# 12_HEADERS.net
KiCad netlist of a schematic drawn in Altium Designer
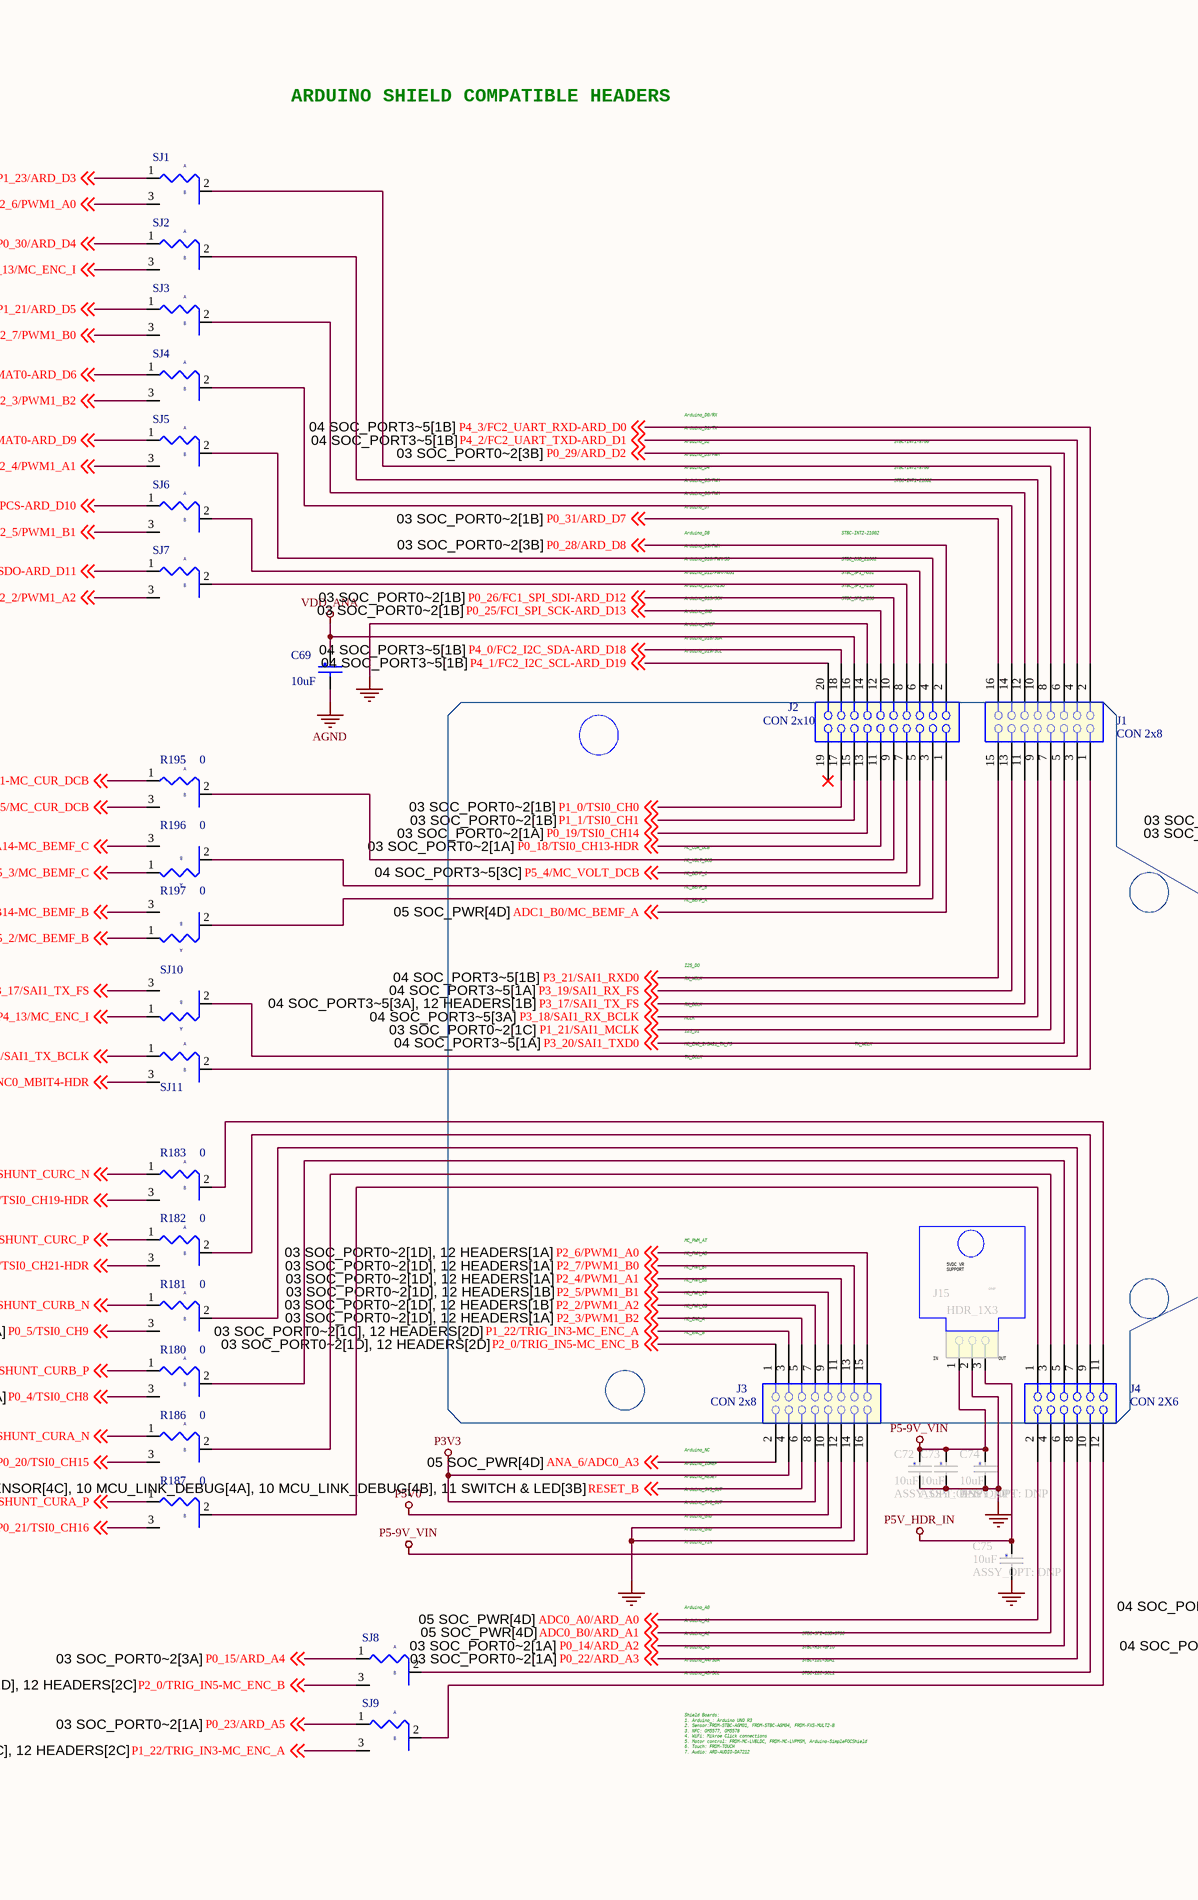
[diagram p0: 12 HEADERS.SchDoc, left]
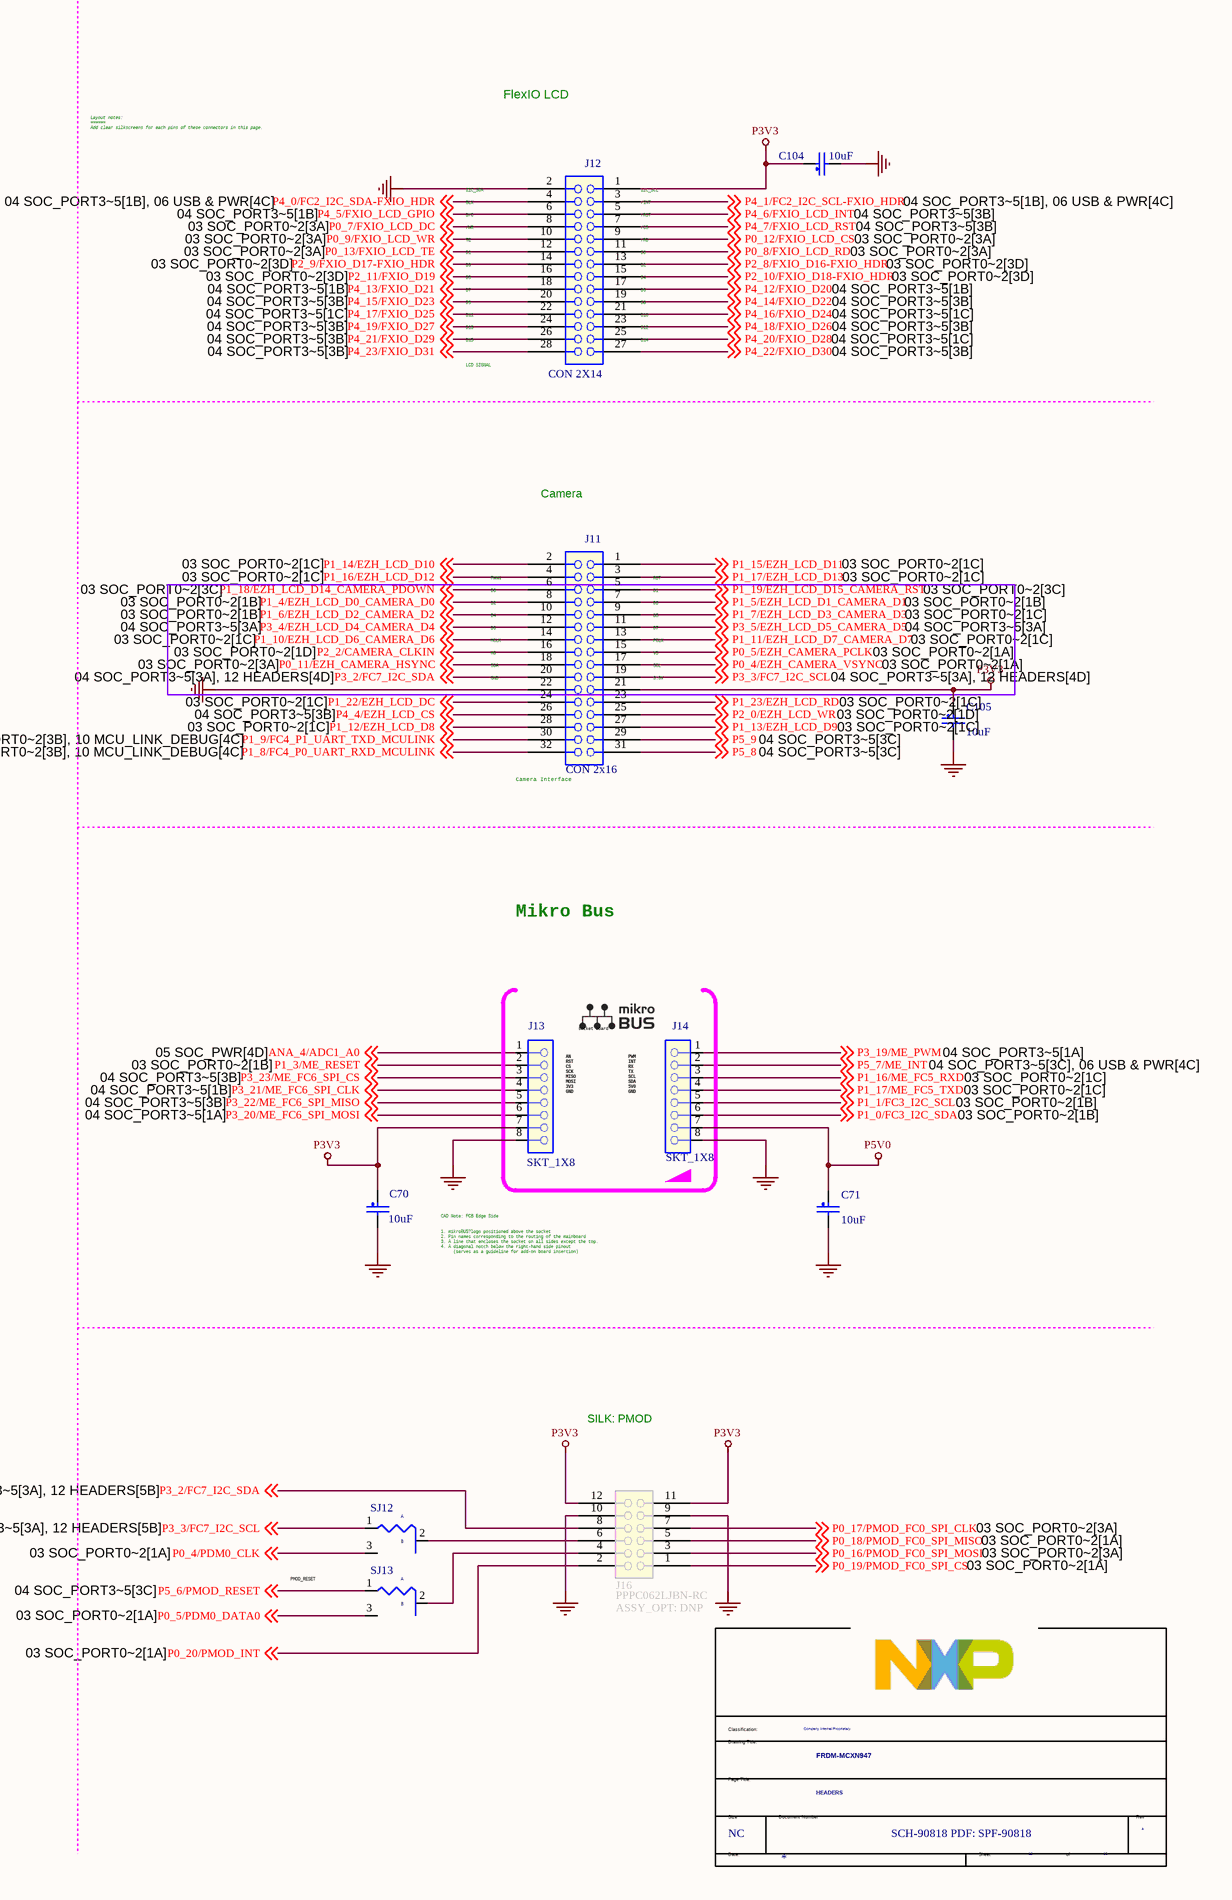
[diagram p1: 12 HEADERS.SchDoc, right]

(export (version "E")
  (design (tool "Eeschema 10.0.6"))
  (components
    (comp (ref "*")
      (value "TitleBlock_FS")
      (fields
        (field (name "DOC") "SCH-90818 PDF: SPF-90818")
        (field (name "REVCODE") "A")
        (field (name "TITLE") "FRDM-MCXN947")
        (field (name "PAGE SIZE") "NC")
        (field (name "PAGE NUMBER") "12")
        (field (name "PAGE COUNT") "13")
        (field (name "PAGETITLE") "HEADERS")
        (field (name "CLASSIFICATION") "Company Internal/Proprietary")
      )
      (libsource (lib "*") (part "TitleBlock_FS"))
    )
    (comp (ref "C69")
      (value "10uF")
      (footprint "CC0603_OV")
      (description "CAP CER 10uF 25V 10% X5R 0603")
      (fields (field (name "TOLERANCE") "10%"))
      (libsource (lib "*") (part "CAP_NP"))
    )
    (comp (ref "C70")
      (value "10uF")
      (footprint "CC0603_OV")
      (description "CAP CER 10uF 25V 10% X5R 0603")
      (fields (field (name "TOLERANCE") "10%"))
      (libsource (lib "*") (part "CAP_NP"))
    )
    (comp (ref "C71")
      (value "10uF")
      (footprint "CC0603_OV")
      (description "CAP CER 10uF 25V 10% X5R 0603")
      (fields (field (name "TOLERANCE") "10%"))
      (libsource (lib "*") (part "CAP_NP"))
    )
    (comp (ref "C72")
      (value "10uF")
      (footprint "CC0603_OV")
      (description "CAP CER 10uF 25V 10% X5R 0603")
      (fields (field (name "ASSY_OPT") "DNP") (field (name "TOLERANCE") "10%"))
      (libsource (lib "*") (part "CAP_NP"))
    )
    (comp (ref "C73")
      (value "10uF")
      (footprint "CC0603_OV")
      (description "CAP CER 10uF 25V 10% X5R 0603")
      (fields (field (name "ASSY_OPT") "DNP") (field (name "TOLERANCE") "10%"))
      (libsource (lib "*") (part "CAP_NP"))
    )
    (comp (ref "C74")
      (value "10uF")
      (footprint "CC0603_OV")
      (description "CAP CER 10uF 25V 10% X5R 0603")
      (fields (field (name "ASSY_OPT") "DNP") (field (name "TOLERANCE") "10%"))
      (libsource (lib "*") (part "CAP_NP"))
    )
    (comp (ref "C75")
      (value "10uF")
      (footprint "CC0603_OV")
      (description "CAP CER 10uF 25V 10% X5R 0603")
      (fields (field (name "ASSY_OPT") "DNP") (field (name "TOLERANCE") "10%"))
      (libsource (lib "*") (part "CAP_NP"))
    )
    (comp (ref "C104")
      (value "10uF")
      (footprint "CC0603_OV")
      (description "CAP CER 10uF 25V 10% X5R 0603")
      (fields (field (name "TOLERANCE") "10%"))
      (libsource (lib "*") (part "CAP_NP"))
    )
    (comp (ref "C105")
      (value "10uF")
      (footprint "CC0603_OV")
      (description "CAP CER 10uF 25V 10% X5R 0603")
      (fields (field (name "TOLERANCE") "10%"))
      (libsource (lib "*") (part "CAP_NP"))
    )
    (comp (ref "J1")
      (value "CON 2x8")
      (footprint "con_2x8_skt_100_th")
      (description "CON 2X8 SKT SHRD TH 100MIL CTR 345H AU 126L")
      (libsource (lib "*") (part "CONN_HDR_8X2"))
    )
    (comp (ref "J2")
      (value "CON 2x10")
      (footprint "con_skt2x10_th")
      (description "CON 2X10 SKT SHRD TH 100MIL CTR 345H AU 126L")
      (libsource (lib "*") (part "CONN_HDR_10X2"))
    )
    (comp (ref "J3")
      (value "CON 2x8")
      (footprint "con_2x8_skt_100_th")
      (description "CON 2X8 SKT SHRD TH 100MIL CTR 345H AU 126L")
      (libsource (lib "") (part "CONN_HDR_8X2_1"))
    )
    (comp (ref "J4")
      (value "CON 2X6")
      (footprint "con_skt2x6_th_126l")
      (description "CON 2X6 SKT SHRD TH 100MIL CTR 345H AU 126L")
      (libsource (lib "*") (part "CONN_HDR_6X2"))
    )
    (comp (ref "J11")
      (value "CON 2x16")
      (footprint "con_skt_32f_100_th")
      (description "CON 2X16 SKT SHRD TH 100MIL CTR 345H AU 126L")
      (fields (field (name "SILK") "Camera"))
      (libsource (lib "*") (part "CONN_HDR_16X2"))
    )
    (comp (ref "J12")
      (value "CON 2X14")
      (footprint "con_skt2x14_th_126l")
      (description "CON 2X14 SKT SHRD TH 100MIL CTR 345H AU 126L")
      (fields (field (name "SILK") "FlexIO LCD"))
      (libsource (lib "*") (part "CONN_HDR_14X2"))
    )
    (comp (ref "J13")
      (value "SKT_1X8")
      (footprint "con_1x8_skt_2p54_th_126l")
      (description "CON 1X8 SKT TH 100MIL SP 344H AU 118L")
      (libsource (lib "*") (part "CONN_HDR_8X1"))
    )
    (comp (ref "J14")
      (value "SKT_1X8")
      (footprint "con_1x8_skt_2p54_th_126l")
      (description "CON 1X8 SKT TH 100MIL SP 344H AU 118L")
      (libsource (lib "") (part "CONN_HDR_8X1_1"))
    )
    (comp (ref "J15")
      (value "HDR_1X3")
      (footprint "HDR103")
      (description "HDR 1X3 TH 100MIL SP 330H AU 98L")
      (fields (field (name "ASSY_OPT") "DNP"))
      (libsource (lib "*") (part "CONN_HDR_3X1"))
    )
    (comp (ref "J16")
      (value "PPPC062LJBN-RC")
      (footprint "skt2x6_100_th_ra")
      (description "CON 2X6 SKT RA TH 100MIL CTR 206H AU 124L")
      (fields (field (name "ASSY_OPT") "DNP") (field (name "SILK") "PMOD"))
      (libsource (lib "*") (part "CONN_HDR_6X2"))
    )
    (comp (ref "R180")
      (value "0")
      (footprint "R603-X2")
      (description "RES MF ZERO OHM 1/10W -- 0603")
      (libsource (lib "*") (part "RES_3PIN"))
    )
    (comp (ref "R181")
      (value "0")
      (footprint "R603-X2")
      (description "RES MF ZERO OHM 1/10W -- 0603")
      (libsource (lib "*") (part "RES_3PIN"))
    )
    (comp (ref "R182")
      (value "0")
      (footprint "R603-X2")
      (description "RES MF ZERO OHM 1/10W -- 0603")
      (libsource (lib "*") (part "RES_3PIN"))
    )
    (comp (ref "R183")
      (value "0")
      (footprint "R603-X2")
      (description "RES MF ZERO OHM 1/10W -- 0603")
      (libsource (lib "*") (part "RES_3PIN"))
    )
    (comp (ref "R186")
      (value "0")
      (footprint "R603-X2")
      (description "RES MF ZERO OHM 1/10W -- 0603")
      (libsource (lib "*") (part "RES_3PIN"))
    )
    (comp (ref "R187")
      (value "0")
      (footprint "R603-X2")
      (description "RES MF ZERO OHM 1/10W -- 0603")
      (libsource (lib "*") (part "RES_3PIN"))
    )
    (comp (ref "R195")
      (value "0")
      (footprint "R603-X2")
      (description "RES MF ZERO OHM 1/10W -- 0603")
      (libsource (lib "*") (part "RES_3PIN"))
    )
    (comp (ref "R196")
      (value "0")
      (footprint "R603-X2")
      (description "RES MF ZERO OHM 1/10W -- 0603")
      (libsource (lib "*") (part "RES_3PIN"))
    )
    (comp (ref "R197")
      (value "0")
      (footprint "R603-X2")
      (description "RES MF ZERO OHM 1/10W -- 0603")
      (libsource (lib "*") (part "RES_3PIN"))
    )
    (comp (ref "SJ1")
      (value "3 PIN 0402 JUMPER")
      (footprint "3pin_0402_solder_blob_jumper_short_psp_a")
      (description "SOLDER BLOB JUMPER 3PIN 1-2 SHORT 0402 - NO PART TO ORDER")
      (libsource (lib "*") (part "RES_3PIN"))
    )
    (comp (ref "SJ2")
      (value "3 PIN 0402 JUMPER")
      (footprint "3pin_0402_solder_blob_jumper_short_psp_a")
      (description "SOLDER BLOB JUMPER 3PIN 1-2 SHORT 0402 - NO PART TO ORDER")
      (libsource (lib "*") (part "RES_3PIN"))
    )
    (comp (ref "SJ3")
      (value "3 PIN 0402 JUMPER")
      (footprint "3pin_0402_solder_blob_jumper_short_psp_a")
      (description "SOLDER BLOB JUMPER 3PIN 1-2 SHORT 0402 - NO PART TO ORDER")
      (libsource (lib "*") (part "RES_3PIN"))
    )
    (comp (ref "SJ4")
      (value "3 PIN 0402 JUMPER")
      (footprint "3pin_0402_solder_blob_jumper_short_psp_a")
      (description "SOLDER BLOB JUMPER 3PIN 1-2 SHORT 0402 - NO PART TO ORDER")
      (libsource (lib "*") (part "RES_3PIN"))
    )
    (comp (ref "SJ5")
      (value "3 PIN 0402 JUMPER")
      (footprint "3pin_0402_solder_blob_jumper_short_psp_a")
      (description "SOLDER BLOB JUMPER 3PIN 1-2 SHORT 0402 - NO PART TO ORDER")
      (libsource (lib "*") (part "RES_3PIN"))
    )
    (comp (ref "SJ6")
      (value "3 PIN 0402 JUMPER")
      (footprint "3pin_0402_solder_blob_jumper_short_psp_a")
      (description "SOLDER BLOB JUMPER 3PIN 1-2 SHORT 0402 - NO PART TO ORDER")
      (libsource (lib "*") (part "RES_3PIN"))
    )
    (comp (ref "SJ7")
      (value "3 PIN 0402 JUMPER")
      (footprint "3pin_0402_solder_blob_jumper_short_psp_a")
      (description "SOLDER BLOB JUMPER 3PIN 1-2 SHORT 0402 - NO PART TO ORDER")
      (libsource (lib "*") (part "RES_3PIN"))
    )
    (comp (ref "SJ8")
      (value "3 PIN 0402 JUMPER")
      (footprint "3pin_0402_solder_blob_jumper_short_psp_a")
      (description "SOLDER BLOB JUMPER 3PIN 1-2 SHORT 0402 - NO PART TO ORDER")
      (libsource (lib "*") (part "RES_3PIN"))
    )
    (comp (ref "SJ9")
      (value "3 PIN 0402 JUMPER")
      (footprint "3pin_0402_solder_blob_jumper_short_psp_a")
      (description "SOLDER BLOB JUMPER 3PIN 1-2 SHORT 0402 - NO PART TO ORDER")
      (libsource (lib "*") (part "RES_3PIN"))
    )
    (comp (ref "SJ10")
      (value "3 PIN 0402 JUMPER")
      (footprint "3pin_0402_solder_blob_jumper_short_psp_a")
      (description "SOLDER BLOB JUMPER 3PIN 1-2 SHORT 0402 - NO PART TO ORDER")
      (libsource (lib "*") (part "RES_3PIN"))
    )
    (comp (ref "SJ11")
      (value "3 PIN 0402 JUMPER")
      (footprint "3pin_0402_solder_blob_jumper_short_psp_a")
      (description "SOLDER BLOB JUMPER 3PIN 1-2 SHORT 0402 - NO PART TO ORDER")
      (libsource (lib "*") (part "RES_3PIN"))
    )
    (comp (ref "SJ12")
      (value "3 PIN 0402 JUMPER")
      (footprint "3pin_0402_solder_blob_jumper_short_psp_a")
      (description "SOLDER BLOB JUMPER 3PIN 1-2 SHORT 0402 - NO PART TO ORDER")
      (libsource (lib "*") (part "RES_3PIN"))
    )
    (comp (ref "SJ13")
      (value "3 PIN 0402 JUMPER")
      (footprint "3pin_0402_solder_blob_jumper_short_psp_a")
      (description "SOLDER BLOB JUMPER 3PIN 1-2 SHORT 0402 - NO PART TO ORDER")
      (libsource (lib "*") (part "RES_3PIN"))
    )
  )
  (nets
    (net (code "1") (name "ADC0_A0{slash}ARD_A0") (class "Default")
      (node (ref "J4") (pin "2") (pinfunction "B1_2") (pintype "passive"))
    )
    (net (code "2") (name "ADC0_B0{slash}ARD_A1") (class "Default")
      (node (ref "J4") (pin "4") (pinfunction "B2_4") (pintype "passive"))
    )
    (net (code "3") (name "ADC1_B0{slash}MC_BEMF_A") (class "Default")
      (node (ref "J2") (pin "1") (pinfunction "1_1") (pintype "passive"))
    )
    (net (code "4") (name "AGND") (class "Default")
      (node (ref "C69") (pin "2") (pinfunction "2_2") (pintype "passive"))
    )
    (net (code "5") (name "ANA_4{slash}ADC1_A0") (class "Default")
      (node (ref "J13") (pin "1") (pinfunction "1_1") (pintype "passive"))
    )
    (net (code "6") (name "ANA_6{slash}ADC0_A3") (class "Default")
      (node (ref "J3") (pin "2") (pinfunction "B1_2") (pintype "passive"))
    )
    (net (code "7") (name "GND") (class "Default")
      (node (ref "C104") (pin "2") (pinfunction "2_2") (pintype "passive"))
      (node (ref "C105") (pin "2") (pinfunction "2_2") (pintype "passive"))
      (node (ref "C70") (pin "2") (pinfunction "2_2") (pintype "passive"))
      (node (ref "C71") (pin "2") (pinfunction "2_2") (pintype "passive"))
      (node (ref "C72") (pin "2") (pinfunction "2_2") (pintype "passive"))
      (node (ref "C73") (pin "2") (pinfunction "2_2") (pintype "passive"))
      (node (ref "C74") (pin "2") (pinfunction "2_2") (pintype "passive"))
      (node (ref "C75") (pin "2") (pinfunction "2_2") (pintype "passive"))
      (node (ref "J11") (pin "22") (pinfunction "B11_22") (pintype "passive"))
      (node (ref "J12") (pin "2") (pinfunction "B1_2") (pintype "passive"))
      (node (ref "J13") (pin "8") (pinfunction "8_8") (pintype "passive"))
      (node (ref "J14") (pin "8") (pinfunction "8_8") (pintype "passive"))
      (node (ref "J15") (pin "2") (pinfunction "2_2") (pintype "passive"))
      (node (ref "J16") (pin "10") (pinfunction "B5_10") (pintype "passive"))
      (node (ref "J16") (pin "9") (pinfunction "A5_9") (pintype "passive"))
      (node (ref "J2") (pin "14") (pinfunction "14_14") (pintype "passive"))
      (node (ref "J3") (pin "12") (pinfunction "B6_12") (pintype "passive"))
      (node (ref "J3") (pin "14") (pinfunction "B7_14") (pintype "passive"))
    )
    (net (code "8") (name "Net-(J1-A1)") (class "Default")
      (node (ref "J1") (pin "1") (pinfunction "A1_1") (pintype "passive"))
      (node (ref "SJ11") (pin "2") (pinfunction "2_2") (pintype "passive"))
    )
    (net (code "9") (name "Net-(J1-A2)") (class "Default")
      (node (ref "J1") (pin "3") (pinfunction "A2_3") (pintype "passive"))
      (node (ref "SJ10") (pin "2") (pinfunction "2_2") (pintype "passive"))
    )
    (net (code "10") (name "Net-(J1-B4)") (class "Default")
      (node (ref "J1") (pin "8") (pinfunction "B4_8") (pintype "passive"))
      (node (ref "SJ1") (pin "2") (pinfunction "2_2") (pintype "passive"))
    )
    (net (code "11") (name "Net-(J1-B5)") (class "Default")
      (node (ref "J1") (pin "10") (pinfunction "B5_10") (pintype "passive"))
      (node (ref "SJ2") (pin "2") (pinfunction "2_2") (pintype "passive"))
    )
    (net (code "12") (name "Net-(J1-B6)") (class "Default")
      (node (ref "J1") (pin "12") (pinfunction "B6_12") (pintype "passive"))
      (node (ref "SJ3") (pin "2") (pinfunction "2_2") (pintype "passive"))
    )
    (net (code "13") (name "Net-(J1-B7)") (class "Default")
      (node (ref "J1") (pin "14") (pinfunction "B7_14") (pintype "passive"))
      (node (ref "SJ4") (pin "2") (pinfunction "2_2") (pintype "passive"))
    )
    (net (code "14") (name "Net-(J2-Pad3)") (class "Default")
      (node (ref "J2") (pin "3") (pinfunction "3_3") (pintype "passive"))
      (node (ref "R197") (pin "2") (pinfunction "2_2") (pintype "passive"))
    )
    (net (code "15") (name "Net-(J2-Pad4)") (class "Default")
      (node (ref "J2") (pin "4") (pinfunction "4_4") (pintype "passive"))
      (node (ref "SJ5") (pin "2") (pinfunction "2_2") (pintype "passive"))
    )
    (net (code "16") (name "Net-(J2-Pad5)") (class "Default")
      (node (ref "J2") (pin "5") (pinfunction "5_5") (pintype "passive"))
      (node (ref "R196") (pin "2") (pinfunction "2_2") (pintype "passive"))
    )
    (net (code "17") (name "Net-(J2-Pad6)") (class "Default")
      (node (ref "J2") (pin "6") (pinfunction "6_6") (pintype "passive"))
      (node (ref "SJ6") (pin "2") (pinfunction "2_2") (pintype "passive"))
    )
    (net (code "18") (name "Net-(J2-Pad8)") (class "Default")
      (node (ref "J2") (pin "8") (pinfunction "8_8") (pintype "passive"))
      (node (ref "SJ7") (pin "2") (pinfunction "2_2") (pintype "passive"))
    )
    (net (code "19") (name "Net-(J2-Pad9)") (class "Default")
      (node (ref "J2") (pin "9") (pinfunction "9_9") (pintype "passive"))
      (node (ref "R195") (pin "2") (pinfunction "2_2") (pintype "passive"))
    )
    (net (code "20") (name "Net-(J4-A1)") (class "Default")
      (node (ref "J4") (pin "1") (pinfunction "A1_1") (pintype "passive"))
      (node (ref "R187") (pin "2") (pinfunction "2_2") (pintype "passive"))
    )
    (net (code "21") (name "Net-(J4-A2)") (class "Default")
      (node (ref "J4") (pin "3") (pinfunction "A2_3") (pintype "passive"))
      (node (ref "R186") (pin "2") (pinfunction "2_2") (pintype "passive"))
    )
    (net (code "22") (name "Net-(J4-A3)") (class "Default")
      (node (ref "J4") (pin "5") (pinfunction "A3_5") (pintype "passive"))
      (node (ref "R180") (pin "2") (pinfunction "2_2") (pintype "passive"))
    )
    (net (code "23") (name "Net-(J4-A4)") (class "Default")
      (node (ref "J4") (pin "7") (pinfunction "A4_7") (pintype "passive"))
      (node (ref "R181") (pin "2") (pinfunction "2_2") (pintype "passive"))
    )
    (net (code "24") (name "Net-(J4-A5)") (class "Default")
      (node (ref "J4") (pin "9") (pinfunction "A5_9") (pintype "passive"))
      (node (ref "R182") (pin "2") (pinfunction "2_2") (pintype "passive"))
    )
    (net (code "25") (name "Net-(J4-A6)") (class "Default")
      (node (ref "J4") (pin "11") (pinfunction "A6_11") (pintype "passive"))
      (node (ref "R183") (pin "2") (pinfunction "2_2") (pintype "passive"))
    )
    (net (code "26") (name "Net-(J4-B5)") (class "Default")
      (node (ref "J4") (pin "10") (pinfunction "B5_10") (pintype "passive"))
      (node (ref "SJ8") (pin "2") (pinfunction "2_2") (pintype "passive"))
    )
    (net (code "27") (name "Net-(J4-B6)") (class "Default")
      (node (ref "J4") (pin "12") (pinfunction "B6_12") (pintype "passive"))
      (node (ref "SJ9") (pin "2") (pinfunction "2_2") (pintype "passive"))
    )
    (net (code "28") (name "Net-(J16-B2)") (class "Default")
      (node (ref "J16") (pin "4") (pinfunction "B2_4") (pintype "passive"))
      (node (ref "SJ13") (pin "2") (pinfunction "2_2") (pintype "passive"))
    )
    (net (code "29") (name "Net-(J16-B3)") (class "Default")
      (node (ref "J16") (pin "6") (pinfunction "B3_6") (pintype "passive"))
      (node (ref "SJ12") (pin "2") (pinfunction "2_2") (pintype "passive"))
    )
    (net (code "30") (name "OPAMP0_INN{slash}RSHUNT_CURA_N") (class "Default")
      (node (ref "R186") (pin "1") (pinfunction "1_1") (pintype "passive"))
    )
    (net (code "31") (name "OPAMP1_INN{slash}RSHUNT_CURB_N") (class "Default")
      (node (ref "R181") (pin "1") (pinfunction "1_1") (pintype "passive"))
    )
    (net (code "32") (name "OPAMP2_INN{slash}RSHUNT_CURC_N") (class "Default")
      (node (ref "R183") (pin "1") (pinfunction "1_1") (pintype "passive"))
    )
    (net (code "33") (name "P0_3{slash}CMP1_IN1-MC_CUR_DCB") (class "Default")
      (node (ref "R195") (pin "1") (pinfunction "1_1") (pintype "passive"))
    )
    (net (code "34") (name "P0_4{slash}EZH_CAMERA_VSYNC") (class "Default")
      (node (ref "J11") (pin "17") (pinfunction "A9_17") (pintype "passive"))
    )
    (net (code "35") (name "P0_4{slash}PDM0_CLK") (class "Default")
      (node (ref "SJ12") (pin "3") (pinfunction "3_3") (pintype "passive"))
    )
    (net (code "36") (name "P0_4{slash}TSI0_CH8") (class "Default")
      (node (ref "R180") (pin "3") (pinfunction "3_3") (pintype "passive"))
    )
    (net (code "37") (name "P0_5{slash}EZH_CAMERA_PCLK") (class "Default")
      (node (ref "J11") (pin "15") (pinfunction "A8_15") (pintype "passive"))
    )
    (net (code "38") (name "P0_5{slash}PDM0_DATA0") (class "Default")
      (node (ref "SJ13") (pin "3") (pinfunction "3_3") (pintype "passive"))
    )
    (net (code "39") (name "P0_5{slash}TSI0_CH9") (class "Default")
      (node (ref "R181") (pin "3") (pinfunction "3_3") (pintype "passive"))
    )
    (net (code "40") (name "P0_7{slash}FXIO_LCD_DC") (class "Default")
      (node (ref "J12") (pin "8") (pinfunction "B4_8") (pintype "passive"))
    )
    (net (code "41") (name "P0_8{slash}FXIO_LCD_RD") (class "Default")
      (node (ref "J12") (pin "11") (pinfunction "A6_11") (pintype "passive"))
    )
    (net (code "42") (name "P0_9{slash}FXIO_LCD_WR") (class "Default")
      (node (ref "J12") (pin "10") (pinfunction "B5_10") (pintype "passive"))
    )
    (net (code "43") (name "P0_10{slash}CT0_MAT0-ARD_D9") (class "Default")
      (node (ref "SJ5") (pin "1") (pinfunction "1_1") (pintype "passive"))
    )
    (net (code "44") (name "P0_11{slash}EZH_CAMERA_HSYNC") (class "Default")
      (node (ref "J11") (pin "18") (pinfunction "B9_18") (pintype "passive"))
    )
    (net (code "45") (name "P0_12{slash}FXIO_LCD_CS") (class "Default")
      (node (ref "J12") (pin "9") (pinfunction "A5_9") (pintype "passive"))
    )
    (net (code "46") (name "P0_13{slash}FXIO_LCD_TE") (class "Default")
      (node (ref "J12") (pin "12") (pinfunction "B6_12") (pintype "passive"))
    )
    (net (code "47") (name "P0_14{slash}ADC0_B14-MC_BEMF_B") (class "Default")
      (node (ref "R197") (pin "3") (pinfunction "3_3") (pintype "passive"))
    )
    (net (code "48") (name "P0_14{slash}ARD_A2") (class "Default")
      (node (ref "J4") (pin "6") (pinfunction "B3_6") (pintype "passive"))
    )
    (net (code "49") (name "P0_15{slash}ARD_A4") (class "Default")
      (node (ref "SJ8") (pin "1") (pinfunction "1_1") (pintype "passive"))
    )
    (net (code "50") (name "P0_16{slash}PMOD_FC0_SPI_MOSI") (class "Default")
      (node (ref "J16") (pin "3") (pinfunction "A2_3") (pintype "passive"))
    )
    (net (code "51") (name "P0_17{slash}PMOD_FC0_SPI_CLK") (class "Default")
      (node (ref "J16") (pin "7") (pinfunction "A4_7") (pintype "passive"))
    )
    (net (code "52") (name "P0_18{slash}PMOD_FC0_SPI_MISO") (class "Default")
      (node (ref "J16") (pin "5") (pinfunction "A3_5") (pintype "passive"))
    )
    (net (code "53") (name "P0_18{slash}TSI0_CH13-HDR") (class "Default")
      (node (ref "J2") (pin "11") (pinfunction "11_11") (pintype "passive"))
    )
    (net (code "54") (name "P0_19{slash}PMOD_FC0_SPI_CS") (class "Default")
      (node (ref "J16") (pin "1") (pinfunction "A1_1") (pintype "passive"))
    )
    (net (code "55") (name "P0_19{slash}TSI0_CH14") (class "Default")
      (node (ref "J2") (pin "13") (pinfunction "13_13") (pintype "passive"))
    )
    (net (code "56") (name "P0_20{slash}PMOD_INT") (class "Default")
      (node (ref "J16") (pin "2") (pinfunction "B1_2") (pintype "passive"))
    )
    (net (code "57") (name "P0_20{slash}TSI0_CH15") (class "Default")
      (node (ref "R186") (pin "3") (pinfunction "3_3") (pintype "passive"))
    )
    (net (code "58") (name "P0_21{slash}TSI0_CH16") (class "Default")
      (node (ref "R187") (pin "3") (pinfunction "3_3") (pintype "passive"))
    )
    (net (code "59") (name "P0_22{slash}ADC0_A14-MC_BEMF_C") (class "Default")
      (node (ref "R196") (pin "3") (pinfunction "3_3") (pintype "passive"))
    )
    (net (code "60") (name "P0_22{slash}ARD_A3") (class "Default")
      (node (ref "J4") (pin "8") (pinfunction "B4_8") (pintype "passive"))
    )
    (net (code "61") (name "P0_23{slash}ARD_A5") (class "Default")
      (node (ref "SJ9") (pin "1") (pinfunction "1_1") (pintype "passive"))
    )
    (net (code "62") (name "P0_24{slash}FC1_SPI_SDO-ARD_D11") (class "Default")
      (node (ref "SJ7") (pin "1") (pinfunction "1_1") (pintype "passive"))
    )
    (net (code "63") (name "P0_25{slash}FCI_SPI_SCK-ARD_D13") (class "Default")
      (node (ref "J2") (pin "12") (pinfunction "12_12") (pintype "passive"))
    )
    (net (code "64") (name "P0_26{slash}FC1_SPI_SDI-ARD_D12") (class "Default")
      (node (ref "J2") (pin "10") (pinfunction "10_10") (pintype "passive"))
    )
    (net (code "65") (name "P0_27{slash}FC1_SPI_PCS-ARD_D10") (class "Default")
      (node (ref "SJ6") (pin "1") (pinfunction "1_1") (pintype "passive"))
    )
    (net (code "66") (name "P0_28{slash}ARD_D8") (class "Default")
      (node (ref "J2") (pin "2") (pinfunction "2_2") (pintype "passive"))
    )
    (net (code "67") (name "P0_29{slash}ARD_D2") (class "Default")
      (node (ref "J1") (pin "6") (pinfunction "B3_6") (pintype "passive"))
    )
    (net (code "68") (name "P0_30{slash}ARD_D4") (class "Default")
      (node (ref "SJ2") (pin "1") (pinfunction "1_1") (pintype "passive"))
    )
    (net (code "69") (name "P0_31{slash}ARD_D7") (class "Default")
      (node (ref "J1") (pin "16") (pinfunction "B8_16") (pintype "passive"))
    )
    (net (code "70") (name "P1_0{slash}FC3_I2C_SDA") (class "Default")
      (node (ref "J14") (pin "6") (pinfunction "6_6") (pintype "passive"))
    )
    (net (code "71") (name "P1_0{slash}TSI0_CH0") (class "Default")
      (node (ref "J2") (pin "17") (pinfunction "17_17") (pintype "passive"))
    )
    (net (code "72") (name "P1_1{slash}FC3_I2C_SCL") (class "Default")
      (node (ref "J14") (pin "5") (pinfunction "5_5") (pintype "passive"))
    )
    (net (code "73") (name "P1_1{slash}TSI0_CH1") (class "Default")
      (node (ref "J2") (pin "15") (pinfunction "15_15") (pintype "passive"))
    )
    (net (code "74") (name "P1_2{slash}CT1_MAT0-ARD_D6") (class "Default")
      (node (ref "SJ4") (pin "1") (pinfunction "1_1") (pintype "passive"))
    )
    (net (code "75") (name "P1_3{slash}ME_RESET") (class "Default")
      (node (ref "J13") (pin "2") (pinfunction "2_2") (pintype "passive"))
    )
    (net (code "76") (name "P1_4{slash}EZH_LCD_D0_CAMERA_D0") (class "Default")
      (node (ref "J11") (pin "8") (pinfunction "B4_8") (pintype "passive"))
    )
    (net (code "77") (name "P1_5{slash}EZH_LCD_D1_CAMERA_D1") (class "Default")
      (node (ref "J11") (pin "7") (pinfunction "A4_7") (pintype "passive"))
    )
    (net (code "78") (name "P1_6{slash}EZH_LCD_D2_CAMERA_D2") (class "Default")
      (node (ref "J11") (pin "10") (pinfunction "B5_10") (pintype "passive"))
    )
    (net (code "79") (name "P1_7{slash}EZH_LCD_D3_CAMERA_D3") (class "Default")
      (node (ref "J11") (pin "9") (pinfunction "A5_9") (pintype "passive"))
    )
    (net (code "80") (name "P1_8{slash}FC4_P0_UART_RXD_MCULINK") (class "Default")
      (node (ref "J11") (pin "32") (pinfunction "B16_32") (pintype "passive"))
    )
    (net (code "81") (name "P1_9{slash}FC4_P1_UART_TXD_MCULINK") (class "Default")
      (node (ref "J11") (pin "30") (pinfunction "B15_30") (pintype "passive"))
    )
    (net (code "82") (name "P1_10{slash}EZH_LCD_D6_CAMERA_D6") (class "Default")
      (node (ref "J11") (pin "14") (pinfunction "B7_14") (pintype "passive"))
    )
    (net (code "83") (name "P1_10{slash}TSI0_CH19-HDR") (class "Default")
      (node (ref "R183") (pin "3") (pinfunction "3_3") (pintype "passive"))
    )
    (net (code "84") (name "P1_11{slash}EZH_LCD_D7_CAMERA_D7") (class "Default")
      (node (ref "J11") (pin "13") (pinfunction "A7_13") (pintype "passive"))
    )
    (net (code "85") (name "P1_12{slash}EZH_LCD_D8") (class "Default")
      (node (ref "J11") (pin "28") (pinfunction "B14_28") (pintype "passive"))
    )
    (net (code "86") (name "P1_12{slash}TSI0_CH21-HDR") (class "Default")
      (node (ref "R182") (pin "3") (pinfunction "3_3") (pintype "passive"))
    )
    (net (code "87") (name "P1_13{slash}EZH_LCD_D9") (class "Default")
      (node (ref "J11") (pin "27") (pinfunction "A14_27") (pintype "passive"))
    )
    (net (code "88") (name "P1_14{slash}EZH_LCD_D10") (class "Default")
      (node (ref "J11") (pin "2") (pinfunction "B1_2") (pintype "passive"))
    )
    (net (code "89") (name "P1_15{slash}EZH_LCD_D11") (class "Default")
      (node (ref "J11") (pin "1") (pinfunction "A1_1") (pintype "passive"))
    )
    (net (code "90") (name "P1_16{slash}EZH_LCD_D12") (class "Default")
      (node (ref "J11") (pin "4") (pinfunction "B2_4") (pintype "passive"))
    )
    (net (code "91") (name "P1_16{slash}ME_FC5_RXD") (class "Default")
      (node (ref "J14") (pin "3") (pinfunction "3_3") (pintype "passive"))
    )
    (net (code "92") (name "P1_17{slash}EZH_LCD_D13") (class "Default")
      (node (ref "J11") (pin "3") (pinfunction "A2_3") (pintype "passive"))
    )
    (net (code "93") (name "P1_17{slash}ME_FC5_TXD") (class "Default")
      (node (ref "J14") (pin "4") (pinfunction "4_4") (pintype "passive"))
    )
    (net (code "94") (name "P1_18{slash}EZH_LCD_D14_CAMERA_PDOWN") (class "Default")
      (node (ref "J11") (pin "6") (pinfunction "B3_6") (pintype "passive"))
    )
    (net (code "95") (name "P1_19{slash}EZH_LCD_D15_CAMERA_RST") (class "Default")
      (node (ref "J11") (pin "5") (pinfunction "A3_5") (pintype "passive"))
    )
    (net (code "96") (name "P1_21{slash}ARD_D5") (class "Default")
      (node (ref "SJ3") (pin "1") (pinfunction "1_1") (pintype "passive"))
    )
    (net (code "97") (name "P1_21{slash}SAI1_MCLK") (class "Default")
      (node (ref "J1") (pin "7") (pinfunction "A4_7") (pintype "passive"))
    )
    (net (code "98") (name "P1_22{slash}EZH_LCD_DC") (class "Default")
      (node (ref "J11") (pin "24") (pinfunction "B12_24") (pintype "passive"))
    )
    (net (code "99") (name "P1_22{slash}TRIG_IN3-MC_ENC_A") (class "Default")
      (node (ref "J3") (pin "3") (pinfunction "A2_3") (pintype "passive"))
      (node (ref "SJ9") (pin "3") (pinfunction "3_3") (pintype "passive"))
    )
    (net (code "100") (name "P1_23{slash}ARD_D3") (class "Default")
      (node (ref "SJ1") (pin "1") (pinfunction "1_1") (pintype "passive"))
    )
    (net (code "101") (name "P1_23{slash}EZH_LCD_RD") (class "Default")
      (node (ref "J11") (pin "23") (pinfunction "A12_23") (pintype "passive"))
    )
    (net (code "102") (name "P2_0{slash}EZH_LCD_WR") (class "Default")
      (node (ref "J11") (pin "25") (pinfunction "A13_25") (pintype "passive"))
    )
    (net (code "103") (name "P2_0{slash}TRIG_IN5-MC_ENC_B") (class "Default")
      (node (ref "J3") (pin "1") (pinfunction "A1_1") (pintype "passive"))
      (node (ref "SJ8") (pin "3") (pinfunction "3_3") (pintype "passive"))
    )
    (net (code "104") (name "P2_2{slash}CAMERA_CLKIN") (class "Default")
      (node (ref "J11") (pin "16") (pinfunction "B8_16") (pintype "passive"))
    )
    (net (code "105") (name "P2_2{slash}PWM1_A2") (class "Default")
      (node (ref "J3") (pin "7") (pinfunction "A4_7") (pintype "passive"))
      (node (ref "SJ7") (pin "3") (pinfunction "3_3") (pintype "passive"))
    )
    (net (code "106") (name "P2_3{slash}PWM1_B2") (class "Default")
      (node (ref "J3") (pin "5") (pinfunction "A3_5") (pintype "passive"))
      (node (ref "SJ4") (pin "3") (pinfunction "3_3") (pintype "passive"))
    )
    (net (code "107") (name "P2_4{slash}PWM1_A1") (class "Default")
      (node (ref "J3") (pin "11") (pinfunction "A6_11") (pintype "passive"))
      (node (ref "SJ5") (pin "3") (pinfunction "3_3") (pintype "passive"))
    )
    (net (code "108") (name "P2_5{slash}PWM1_B1") (class "Default")
      (node (ref "J3") (pin "9") (pinfunction "A5_9") (pintype "passive"))
      (node (ref "SJ6") (pin "3") (pinfunction "3_3") (pintype "passive"))
    )
    (net (code "109") (name "P2_6{slash}PWM1_A0") (class "Default")
      (node (ref "J3") (pin "15") (pinfunction "A8_15") (pintype "passive"))
      (node (ref "SJ1") (pin "3") (pinfunction "3_3") (pintype "passive"))
    )
    (net (code "110") (name "P2_7{slash}PWM1_B0") (class "Default")
      (node (ref "J3") (pin "13") (pinfunction "A7_13") (pintype "passive"))
      (node (ref "SJ3") (pin "3") (pinfunction "3_3") (pintype "passive"))
    )
    (net (code "111") (name "P2_8{slash}FXIO_D16-FXIO_HDR") (class "Default")
      (node (ref "J12") (pin "13") (pinfunction "A7_13") (pintype "passive"))
    )
    (net (code "112") (name "P2_9{slash}FXIO_D17-FXIO_HDR") (class "Default")
      (node (ref "J12") (pin "14") (pinfunction "B7_14") (pintype "passive"))
    )
    (net (code "113") (name "P2_10{slash}FXIO_D18-FXIO_HDR") (class "Default")
      (node (ref "J12") (pin "15") (pinfunction "A8_15") (pintype "passive"))
    )
    (net (code "114") (name "P2_11{slash}FXIO_D19") (class "Default")
      (node (ref "J12") (pin "16") (pinfunction "B8_16") (pintype "passive"))
    )
    (net (code "115") (name "P3V3") (class "Default")
      (node (ref "C104") (pin "1") (pinfunction "1_1") (pintype "passive"))
      (node (ref "C105") (pin "1") (pinfunction "1_1") (pintype "passive"))
      (node (ref "C70") (pin "1") (pinfunction "1_1") (pintype "passive"))
      (node (ref "J11") (pin "21") (pinfunction "A11_21") (pintype "passive"))
      (node (ref "J12") (pin "1") (pinfunction "A1_1") (pintype "passive"))
      (node (ref "J13") (pin "7") (pinfunction "7_7") (pintype "passive"))
      (node (ref "J16") (pin "11") (pinfunction "A6_11") (pintype "passive"))
      (node (ref "J16") (pin "12") (pinfunction "B6_12") (pintype "passive"))
      (node (ref "J3") (pin "4") (pinfunction "B2_4") (pintype "passive"))
      (node (ref "J3") (pin "8") (pinfunction "B4_8") (pintype "passive"))
    )
    (net (code "116") (name "P3_2{slash}FC7_I2C_SDA") (class "Default")
      (node (ref "J11") (pin "20") (pinfunction "B10_20") (pintype "passive"))
      (node (ref "J16") (pin "8") (pinfunction "B4_8") (pintype "passive"))
    )
    (net (code "117") (name "P3_3{slash}FC7_I2C_SCL") (class "Default")
      (node (ref "J11") (pin "19") (pinfunction "A10_19") (pintype "passive"))
      (node (ref "SJ12") (pin "1") (pinfunction "1_1") (pintype "passive"))
    )
    (net (code "118") (name "P3_4{slash}EZH_LCD_D4_CAMERA_D4") (class "Default")
      (node (ref "J11") (pin "12") (pinfunction "B6_12") (pintype "passive"))
    )
    (net (code "119") (name "P3_5{slash}EZH_LCD_D5_CAMERA_D5") (class "Default")
      (node (ref "J11") (pin "11") (pinfunction "A6_11") (pintype "passive"))
    )
    (net (code "120") (name "P3_16{slash}SAI1_TX_BCLK") (class "Default")
      (node (ref "SJ11") (pin "1") (pinfunction "1_1") (pintype "passive"))
    )
    (net (code "121") (name "P3_17{slash}SAI1_TX_FS") (class "Default")
      (node (ref "J1") (pin "11") (pinfunction "A6_11") (pintype "passive"))
      (node (ref "SJ10") (pin "3") (pinfunction "3_3") (pintype "passive"))
    )
    (net (code "122") (name "P3_18{slash}SAI1_RX_BCLK") (class "Default")
      (node (ref "J1") (pin "9") (pinfunction "A5_9") (pintype "passive"))
    )
    (net (code "123") (name "P3_19{slash}ME_PWM") (class "Default")
      (node (ref "J14") (pin "1") (pinfunction "1_1") (pintype "passive"))
    )
    (net (code "124") (name "P3_19{slash}SAI1_RX_FS") (class "Default")
      (node (ref "J1") (pin "13") (pinfunction "A7_13") (pintype "passive"))
    )
    (net (code "125") (name "P3_20{slash}ME_FC6_SPI_MOSI") (class "Default")
      (node (ref "J13") (pin "6") (pinfunction "6_6") (pintype "passive"))
    )
    (net (code "126") (name "P3_20{slash}SAI1_TXD0") (class "Default")
      (node (ref "J1") (pin "5") (pinfunction "A3_5") (pintype "passive"))
    )
    (net (code "127") (name "P3_21{slash}ME_FC6_SPI_CLK") (class "Default")
      (node (ref "J13") (pin "4") (pinfunction "4_4") (pintype "passive"))
    )
    (net (code "128") (name "P3_21{slash}SAI1_RXD0") (class "Default")
      (node (ref "J1") (pin "15") (pinfunction "A8_15") (pintype "passive"))
    )
    (net (code "129") (name "P3_22{slash}ME_FC6_SPI_MISO") (class "Default")
      (node (ref "J13") (pin "5") (pinfunction "5_5") (pintype "passive"))
    )
    (net (code "130") (name "P3_23{slash}ME_FC6_SPI_CS") (class "Default")
      (node (ref "J13") (pin "3") (pinfunction "3_3") (pintype "passive"))
    )
    (net (code "131") (name "P4_0{slash}FC2_I2C_SDA-ARD_D18") (class "Default")
      (node (ref "J2") (pin "18") (pinfunction "18_18") (pintype "passive"))
    )
    (net (code "132") (name "P4_0{slash}FC2_I2C_SDA-FXIO_HDR") (class "Default")
      (node (ref "J12") (pin "4") (pinfunction "B2_4") (pintype "passive"))
    )
    (net (code "133") (name "P4_1{slash}FC2_I2C_SCL-ARD_D19") (class "Default")
      (node (ref "J2") (pin "20") (pinfunction "20_20") (pintype "passive"))
    )
    (net (code "134") (name "P4_1{slash}FC2_I2C_SCL-FXIO_HDR") (class "Default")
      (node (ref "J12") (pin "3") (pinfunction "A2_3") (pintype "passive"))
    )
    (net (code "135") (name "P4_2{slash}FC2_UART_TXD-ARD_D1") (class "Default")
      (node (ref "J1") (pin "4") (pinfunction "B2_4") (pintype "passive"))
    )
    (net (code "136") (name "P4_3{slash}FC2_UART_RXD-ARD_D0") (class "Default")
      (node (ref "J1") (pin "2") (pinfunction "B1_2") (pintype "passive"))
    )
    (net (code "137") (name "P4_4{slash}EZH_LCD_CS") (class "Default")
      (node (ref "J11") (pin "26") (pinfunction "B13_26") (pintype "passive"))
    )
    (net (code "138") (name "P4_5{slash}FXIO_LCD_GPIO") (class "Default")
      (node (ref "J12") (pin "6") (pinfunction "B3_6") (pintype "passive"))
    )
    (net (code "139") (name "P4_5{slash}SINC0_MBIT4-HDR") (class "Default")
      (node (ref "SJ11") (pin "3") (pinfunction "3_3") (pintype "passive"))
    )
    (net (code "140") (name "P4_6{slash}FXIO_LCD_INT") (class "Default")
      (node (ref "J12") (pin "5") (pinfunction "A3_5") (pintype "passive"))
    )
    (net (code "141") (name "P4_7{slash}FXIO_LCD_RST") (class "Default")
      (node (ref "J12") (pin "7") (pinfunction "A4_7") (pintype "passive"))
    )
    (net (code "142") (name "P4_12{slash}FXIO_D20") (class "Default")
      (node (ref "J12") (pin "17") (pinfunction "A9_17") (pintype "passive"))
    )
    (net (code "143") (name "P4_12{slash}RSHUNT_CURA_P") (class "Default")
      (node (ref "R187") (pin "1") (pinfunction "1_1") (pintype "passive"))
    )
    (net (code "144") (name "P4_13{slash}FXIO_D21") (class "Default")
      (node (ref "J12") (pin "18") (pinfunction "B9_18") (pintype "passive"))
    )
    (net (code "145") (name "P4_13{slash}MC_ENC_I") (class "Default")
      (node (ref "SJ10") (pin "1") (pinfunction "1_1") (pintype "passive"))
      (node (ref "SJ2") (pin "3") (pinfunction "3_3") (pintype "passive"))
    )
    (net (code "146") (name "P4_14{slash}FXIO_D22") (class "Default")
      (node (ref "J12") (pin "19") (pinfunction "A10_19") (pintype "passive"))
    )
    (net (code "147") (name "P4_15{slash}FXIO_D23") (class "Default")
      (node (ref "J12") (pin "20") (pinfunction "B10_20") (pintype "passive"))
    )
    (net (code "148") (name "P4_16{slash}FXIO_D24") (class "Default")
      (node (ref "J12") (pin "21") (pinfunction "A11_21") (pintype "passive"))
    )
    (net (code "149") (name "P4_16{slash}RSHUNT_CURB_P") (class "Default")
      (node (ref "R180") (pin "1") (pinfunction "1_1") (pintype "passive"))
    )
    (net (code "150") (name "P4_17{slash}FXIO_D25") (class "Default")
      (node (ref "J12") (pin "22") (pinfunction "B11_22") (pintype "passive"))
    )
    (net (code "151") (name "P4_18{slash}FXIO_D26") (class "Default")
      (node (ref "J12") (pin "23") (pinfunction "A12_23") (pintype "passive"))
    )
    (net (code "152") (name "P4_19{slash}FXIO_D27") (class "Default")
      (node (ref "J12") (pin "24") (pinfunction "B12_24") (pintype "passive"))
    )
    (net (code "153") (name "P4_20{slash}FXIO_D28") (class "Default")
      (node (ref "J12") (pin "25") (pinfunction "A13_25") (pintype "passive"))
    )
    (net (code "154") (name "P4_20{slash}RSHUNT_CURC_P") (class "Default")
      (node (ref "R182") (pin "1") (pinfunction "1_1") (pintype "passive"))
    )
    (net (code "155") (name "P4_21{slash}FXIO_D29") (class "Default")
      (node (ref "J12") (pin "26") (pinfunction "B13_26") (pintype "passive"))
    )
    (net (code "156") (name "P4_22{slash}FXIO_D30") (class "Default")
      (node (ref "J12") (pin "27") (pinfunction "A14_27") (pintype "passive"))
    )
    (net (code "157") (name "P4_23{slash}FXIO_D31") (class "Default")
      (node (ref "J12") (pin "28") (pinfunction "B14_28") (pintype "passive"))
    )
    (net (code "158") (name "P5-9V_VIN") (class "Default")
      (node (ref "C72") (pin "1") (pinfunction "1_1") (pintype "passive"))
      (node (ref "C73") (pin "1") (pinfunction "1_1") (pintype "passive"))
      (node (ref "C74") (pin "1") (pinfunction "1_1") (pintype "passive"))
      (node (ref "J15") (pin "1") (pinfunction "1_1") (pintype "passive"))
      (node (ref "J3") (pin "16") (pinfunction "B8_16") (pintype "passive"))
    )
    (net (code "159") (name "P5V0") (class "Default")
      (node (ref "C71") (pin "1") (pinfunction "1_1") (pintype "passive"))
      (node (ref "J14") (pin "7") (pinfunction "7_7") (pintype "passive"))
      (node (ref "J3") (pin "10") (pinfunction "B5_10") (pintype "passive"))
    )
    (net (code "160") (name "P5V_HDR_IN") (class "Default")
      (node (ref "C75") (pin "1") (pinfunction "1_1") (pintype "passive"))
      (node (ref "J15") (pin "3") (pinfunction "3_3") (pintype "passive"))
    )
    (net (code "161") (name "P5_2{slash}MC_BEMF_B") (class "Default")
      (node (ref "R197") (pin "1") (pinfunction "1_1") (pintype "passive"))
    )
    (net (code "162") (name "P5_3{slash}MC_BEMF_C") (class "Default")
      (node (ref "R196") (pin "1") (pinfunction "1_1") (pintype "passive"))
    )
    (net (code "163") (name "P5_4{slash}MC_VOLT_DCB") (class "Default")
      (node (ref "J2") (pin "7") (pinfunction "7_7") (pintype "passive"))
    )
    (net (code "164") (name "P5_5{slash}MC_CUR_DCB") (class "Default")
      (node (ref "R195") (pin "3") (pinfunction "3_3") (pintype "passive"))
    )
    (net (code "165") (name "P5_6{slash}PMOD_RESET") (class "Default")
      (node (ref "SJ13") (pin "1") (pinfunction "1_1") (pintype "passive"))
    )
    (net (code "166") (name "P5_7{slash}ME_INT") (class "Default")
      (node (ref "J14") (pin "2") (pinfunction "2_2") (pintype "passive"))
    )
    (net (code "167") (name "P5_8") (class "Default")
      (node (ref "J11") (pin "31") (pinfunction "A16_31") (pintype "passive"))
    )
    (net (code "168") (name "P5_9") (class "Default")
      (node (ref "J11") (pin "29") (pinfunction "A15_29") (pintype "passive"))
    )
    (net (code "169") (name "RESET_B") (class "Default")
      (node (ref "J3") (pin "6") (pinfunction "B3_6") (pintype "passive"))
    )
    (net (code "170") (name "VDD_ANA") (class "Default")
      (node (ref "C69") (pin "1") (pinfunction "1_1") (pintype "passive"))
      (node (ref "J2") (pin "16") (pinfunction "16_16") (pintype "passive"))
    )
    (net (code "171") (name "unconnected-(J2-Pad19)") (class "Default")
      (node (ref "J2") (pin "19") (pinfunction "19_19") (pintype "passive+no_connect"))
    )
  )
)
